# Main.net
KiCad netlist of a schematic drawn in Altium Designer
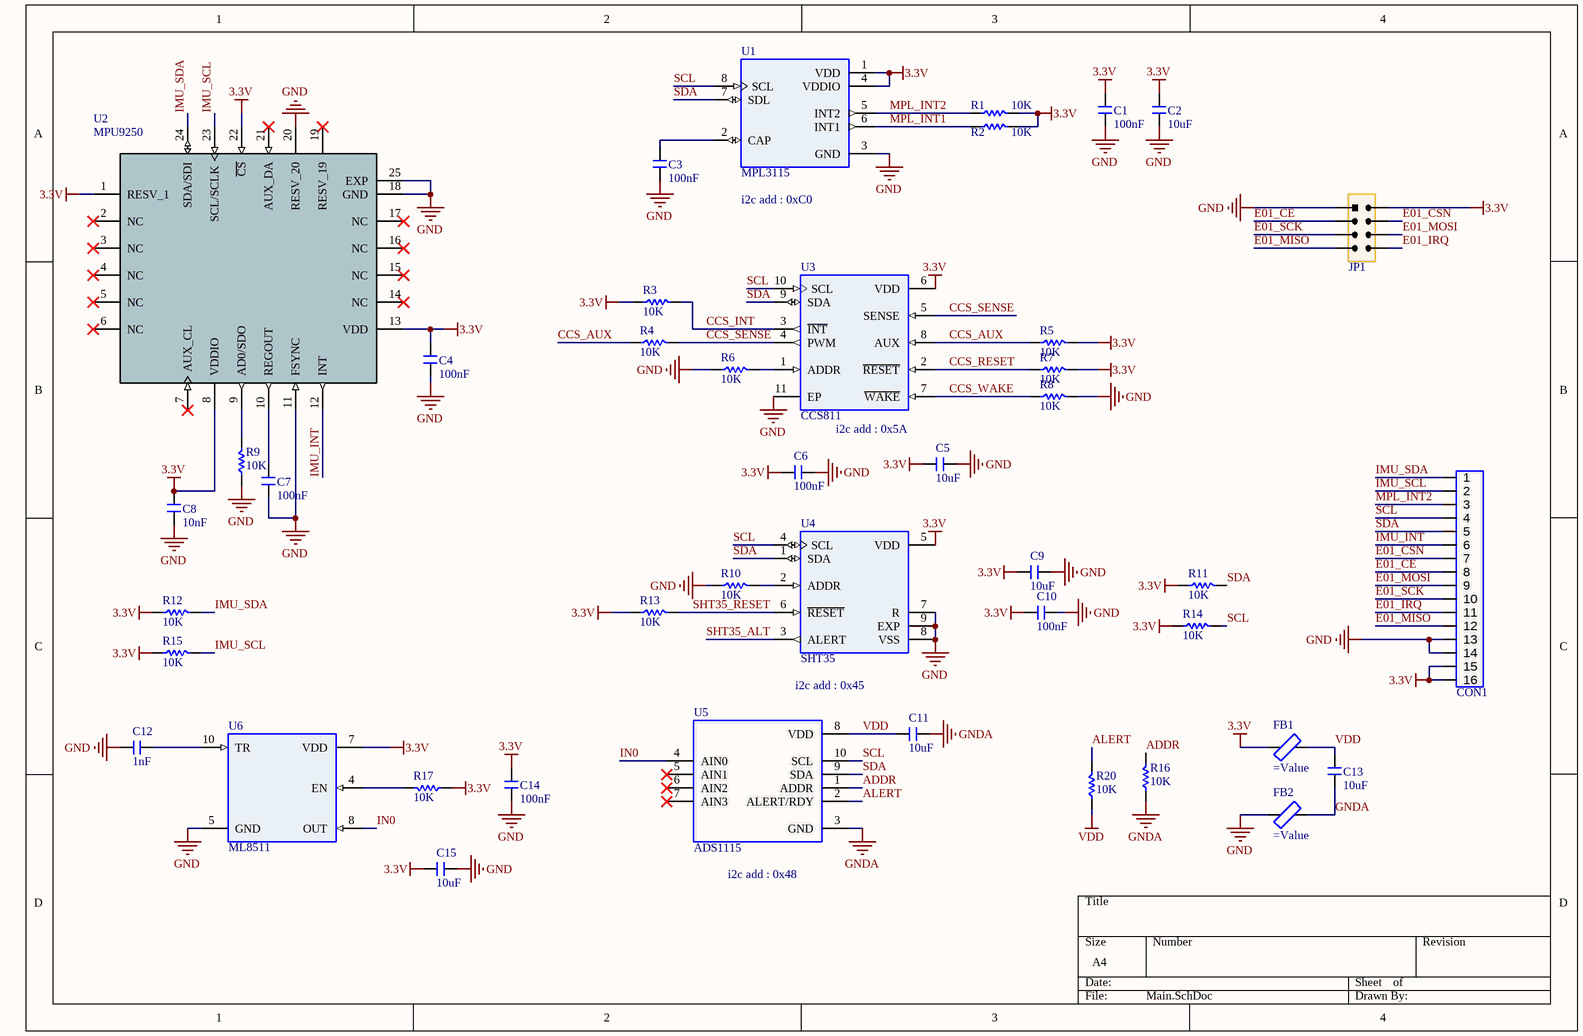
[diagram p0: Main.SchDoc]

(export (version "E")
  (design (tool "Eeschema 10.0.6"))
  (components
    (comp (ref "C1")
      (value "100nF")
      (footprint "C 0603")
      (description "Non-polar patch capacitor")
      (fields (field (name "版权归属") "源创客"))
      (libsource (lib "Passive (Resistor-Capacitor-Inductor-Veristor-Ferrite)") (part "C"))
    )
    (comp (ref "C2")
      (value "10uF")
      (footprint "C 0603")
      (description "Non-polar patch capacitor")
      (fields (field (name "版权归属") "源创客"))
      (libsource (lib "Passive (Resistor-Capacitor-Inductor-Veristor-Ferrite)") (part "C"))
    )
    (comp (ref "C3")
      (value "100nF")
      (footprint "C 0603")
      (description "Non-polar patch capacitor")
      (fields (field (name "版权归属") "源创客"))
      (libsource (lib "Passive (Resistor-Capacitor-Inductor-Veristor-Ferrite)") (part "C"))
    )
    (comp (ref "C4")
      (value "100nF")
      (footprint "C 0603")
      (description "Non-polar patch capacitor")
      (fields (field (name "版权归属") "源创客"))
      (libsource (lib "Passive (Resistor-Capacitor-Inductor-Veristor-Ferrite)") (part "C"))
    )
    (comp (ref "C5")
      (value "10uF")
      (footprint "C 0603")
      (description "Non-polar patch capacitor")
      (fields (field (name "版权归属") "源创客"))
      (libsource (lib "Passive (Resistor-Capacitor-Inductor-Veristor-Ferrite)") (part "C"))
    )
    (comp (ref "C6")
      (value "100nF")
      (footprint "C 0603")
      (description "Non-polar patch capacitor")
      (fields (field (name "版权归属") "源创客"))
      (libsource (lib "Passive (Resistor-Capacitor-Inductor-Veristor-Ferrite)") (part "C"))
    )
    (comp (ref "C7")
      (value "100nF")
      (footprint "C 0603")
      (description "Non-polar patch capacitor")
      (fields (field (name "版权归属") "源创客"))
      (libsource (lib "Passive (Resistor-Capacitor-Inductor-Veristor-Ferrite)") (part "C"))
    )
    (comp (ref "C8")
      (value "10nF")
      (footprint "C 0603")
      (description "Non-polar patch capacitor")
      (fields (field (name "版权归属") "源创客"))
      (libsource (lib "Passive (Resistor-Capacitor-Inductor-Veristor-Ferrite)") (part "C"))
    )
    (comp (ref "C9")
      (value "10uF")
      (footprint "C 0603")
      (description "Non-polar patch capacitor")
      (fields (field (name "版权归属") "源创客"))
      (libsource (lib "Passive (Resistor-Capacitor-Inductor-Veristor-Ferrite)") (part "C"))
    )
    (comp (ref "C10")
      (value "100nF")
      (footprint "C 0603")
      (description "Non-polar patch capacitor")
      (fields (field (name "版权归属") "源创客"))
      (libsource (lib "Passive (Resistor-Capacitor-Inductor-Veristor-Ferrite)") (part "C"))
    )
    (comp (ref "C11")
      (value "10uF")
      (footprint "C 0603")
      (description "Non-polar patch capacitor")
      (fields (field (name "版权归属") "源创客"))
      (libsource (lib "Passive (Resistor-Capacitor-Inductor-Veristor-Ferrite)") (part "C"))
    )
    (comp (ref "C12")
      (value "1nF")
      (footprint "C 0603")
      (description "Non-polar patch capacitor")
      (fields (field (name "版权归属") "源创客"))
      (libsource (lib "Passive (Resistor-Capacitor-Inductor-Veristor-Ferrite)") (part "C"))
    )
    (comp (ref "C13")
      (value "10uF")
      (footprint "C 0603")
      (description "Non-polar patch capacitor")
      (fields (field (name "版权归属") "源创客"))
      (libsource (lib "Passive (Resistor-Capacitor-Inductor-Veristor-Ferrite)") (part "C"))
    )
    (comp (ref "C14")
      (value "100nF")
      (footprint "C 0603")
      (description "Non-polar patch capacitor")
      (fields (field (name "版权归属") "源创客"))
      (libsource (lib "Passive (Resistor-Capacitor-Inductor-Veristor-Ferrite)") (part "C"))
    )
    (comp (ref "C15")
      (value "10uF")
      (footprint "C 0603")
      (description "Non-polar patch capacitor")
      (fields (field (name "版权归属") "源创客"))
      (libsource (lib "Passive (Resistor-Capacitor-Inductor-Veristor-Ferrite)") (part "C"))
    )
    (comp (ref "CON1")
      (value "FFC_0.5_16")
      (footprint "FFC_0.5_16")
      (description "FFC")
      (libsource (lib "FPC") (part "FFC_0.5_16"))
    )
    (comp (ref "FB1")
      (value "~")
      (footprint "F 0603")
      (description "Ferrite Bead")
      (fields (field (name "版权归属") "源创客"))
      (libsource (lib "Passive (Resistor-Capacitor-Inductor-Veristor-Ferrite)") (part "FB"))
    )
    (comp (ref "FB2")
      (value "~")
      (footprint "F 0603")
      (description "Ferrite Bead")
      (fields (field (name "版权归属") "源创客"))
      (libsource (lib "Passive (Resistor-Capacitor-Inductor-Veristor-Ferrite)") (part "FB"))
    )
    (comp (ref "JP1")
      (value "Header 4X2")
      (footprint "HDR-4X2")
      (description "4*2P Connector")
      (fields (field (name "版权归属") "源创客"))
      (libsource (lib "Connectors") (part "Header 4X2"))
    )
    (comp (ref "R1")
      (value "10K")
      (footprint "R 0603")
      (description "Chip resistor")
      (fields (field (name "版权归属") "源创客"))
      (libsource (lib "Passive (Resistor-Capacitor-Inductor-Veristor-Ferrite)") (part "R"))
    )
    (comp (ref "R2")
      (value "10K")
      (footprint "R 0603")
      (description "Chip resistor")
      (fields (field (name "版权归属") "源创客"))
      (libsource (lib "Passive (Resistor-Capacitor-Inductor-Veristor-Ferrite)") (part "R"))
    )
    (comp (ref "R3")
      (value "10K")
      (footprint "R 0603")
      (description "Chip resistor")
      (fields (field (name "版权归属") "源创客"))
      (libsource (lib "Passive (Resistor-Capacitor-Inductor-Veristor-Ferrite)") (part "R"))
    )
    (comp (ref "R4")
      (value "10K")
      (footprint "R 0603")
      (description "Chip resistor")
      (fields (field (name "版权归属") "源创客"))
      (libsource (lib "Passive (Resistor-Capacitor-Inductor-Veristor-Ferrite)") (part "R"))
    )
    (comp (ref "R5")
      (value "10K")
      (footprint "R 0603")
      (description "Chip resistor")
      (fields (field (name "版权归属") "源创客"))
      (libsource (lib "Passive (Resistor-Capacitor-Inductor-Veristor-Ferrite)") (part "R"))
    )
    (comp (ref "R6")
      (value "10K")
      (footprint "R 0603")
      (description "Chip resistor")
      (fields (field (name "版权归属") "源创客"))
      (libsource (lib "Passive (Resistor-Capacitor-Inductor-Veristor-Ferrite)") (part "R"))
    )
    (comp (ref "R7")
      (value "10K")
      (footprint "R 0603")
      (description "Chip resistor")
      (fields (field (name "版权归属") "源创客"))
      (libsource (lib "Passive (Resistor-Capacitor-Inductor-Veristor-Ferrite)") (part "R"))
    )
    (comp (ref "R8")
      (value "10K")
      (footprint "R 0603")
      (description "Chip resistor")
      (fields (field (name "版权归属") "源创客"))
      (libsource (lib "Passive (Resistor-Capacitor-Inductor-Veristor-Ferrite)") (part "R"))
    )
    (comp (ref "R9")
      (value "10K")
      (footprint "R 0603")
      (description "Chip resistor")
      (fields (field (name "版权归属") "源创客"))
      (libsource (lib "Passive (Resistor-Capacitor-Inductor-Veristor-Ferrite)") (part "R"))
    )
    (comp (ref "R10")
      (value "10K")
      (footprint "R 0603")
      (description "Chip resistor")
      (fields (field (name "版权归属") "源创客"))
      (libsource (lib "Passive (Resistor-Capacitor-Inductor-Veristor-Ferrite)") (part "R"))
    )
    (comp (ref "R11")
      (value "10K")
      (footprint "R 0603")
      (description "Chip resistor")
      (fields (field (name "版权归属") "源创客"))
      (libsource (lib "Passive (Resistor-Capacitor-Inductor-Veristor-Ferrite)") (part "R"))
    )
    (comp (ref "R12")
      (value "10K")
      (footprint "R 0603")
      (description "Chip resistor")
      (fields (field (name "版权归属") "源创客"))
      (libsource (lib "Passive (Resistor-Capacitor-Inductor-Veristor-Ferrite)") (part "R"))
    )
    (comp (ref "R13")
      (value "10K")
      (footprint "R 0603")
      (description "Chip resistor")
      (fields (field (name "版权归属") "源创客"))
      (libsource (lib "Passive (Resistor-Capacitor-Inductor-Veristor-Ferrite)") (part "R"))
    )
    (comp (ref "R14")
      (value "10K")
      (footprint "R 0603")
      (description "Chip resistor")
      (fields (field (name "版权归属") "源创客"))
      (libsource (lib "Passive (Resistor-Capacitor-Inductor-Veristor-Ferrite)") (part "R"))
    )
    (comp (ref "R15")
      (value "10K")
      (footprint "R 0603")
      (description "Chip resistor")
      (fields (field (name "版权归属") "源创客"))
      (libsource (lib "Passive (Resistor-Capacitor-Inductor-Veristor-Ferrite)") (part "R"))
    )
    (comp (ref "R16")
      (value "10K")
      (footprint "R 0603")
      (description "Chip resistor")
      (fields (field (name "版权归属") "源创客"))
      (libsource (lib "Passive (Resistor-Capacitor-Inductor-Veristor-Ferrite)") (part "R"))
    )
    (comp (ref "R17")
      (value "10K")
      (footprint "R 0603")
      (description "Chip resistor")
      (fields (field (name "版权归属") "源创客"))
      (libsource (lib "Passive (Resistor-Capacitor-Inductor-Veristor-Ferrite)") (part "R"))
    )
    (comp (ref "R20")
      (value "10K")
      (footprint "R 0603")
      (description "Chip resistor")
      (fields (field (name "版权归属") "源创客"))
      (libsource (lib "Passive (Resistor-Capacitor-Inductor-Veristor-Ferrite)") (part "R"))
    )
    (comp (ref "U1")
      (value "MPL3115")
      (footprint "MPL3115")
      (description "Pressure Sensor")
      (libsource (lib "Sensing Element") (part "MPL3115"))
    )
    (comp (ref "U2")
      (value "MPU9250")
      (footprint "QFN40-25N")
      (libsource (lib "Integrated Circuit") (part "MPU9250"))
    )
    (comp (ref "U3")
      (value "CCS811")
      (footprint "CCS811")
      (libsource (lib "Sensing Element") (part "CCS811"))
    )
    (comp (ref "U4") (value "SHT35") (footprint "SHT35") (libsource (lib "Sensing Element") (part "SHT35")))
    (comp (ref "U5")
      (value "ADS1115")
      (footprint "VSSOP10-N")
      (fields (field (name "版权归属") "源创客"))
      (libsource (lib "Integrated Circuit") (part "ADS1115"))
    )
    (comp (ref "U6")
      (value "ML8511")
      (footprint "ML8511")
      (description "UV Sensor")
      (libsource (lib "Sensing Element") (part "ML8511"))
    )
  )
  (nets
    (net (code "1") (name "/ADDR") (class "Default")
      (node (ref "R16") (pin "2") (pinfunction "2_2") (pintype "passive"))
      (node (ref "U5") (pin "1") (pinfunction "ADDR_1") (pintype "passive"))
    )
    (net (code "2") (name "/ALERT") (class "Default")
      (node (ref "R20") (pin "2") (pinfunction "2_2") (pintype "passive"))
      (node (ref "U5") (pin "2") (pinfunction "ALERT/RDY_2") (pintype "passive"))
    )
    (net (code "3") (name "/CCS_AUX") (class "Default")
      (node (ref "R4") (pin "1") (pinfunction "1_1") (pintype "passive"))
      (node (ref "R5") (pin "1") (pinfunction "1_1") (pintype "passive"))
      (node (ref "U3") (pin "8") (pinfunction "AUX_8") (pintype "input"))
    )
    (net (code "4") (name "/CCS_INT") (class "Default")
      (node (ref "R3") (pin "2") (pinfunction "2_2") (pintype "passive"))
      (node (ref "U3") (pin "3") (pinfunction "~{INT}_3") (pintype "output"))
    )
    (net (code "5") (name "/CCS_RESET") (class "Default")
      (node (ref "R7") (pin "1") (pinfunction "1_1") (pintype "passive"))
      (node (ref "U3") (pin "2") (pinfunction "~{RESET}_2") (pintype "input"))
    )
    (net (code "6") (name "/CCS_SENSE") (class "Default")
      (node (ref "R4") (pin "2") (pinfunction "2_2") (pintype "passive"))
      (node (ref "U3") (pin "4") (pinfunction "PWM_4") (pintype "output"))
      (node (ref "U3") (pin "5") (pinfunction "SENSE_5") (pintype "input"))
    )
    (net (code "7") (name "/CCS_WAKE") (class "Default")
      (node (ref "R8") (pin "1") (pinfunction "1_1") (pintype "passive"))
      (node (ref "U3") (pin "7") (pinfunction "~{WAKE}_7") (pintype "input"))
    )
    (net (code "8") (name "/E01_CE") (class "Default")
      (node (ref "CON1") (pin "8") (pinfunction "8_8") (pintype "passive"))
      (node (ref "JP1") (pin "3") (pintype "passive"))
    )
    (net (code "9") (name "/E01_CSN") (class "Default")
      (node (ref "CON1") (pin "7") (pinfunction "7_7") (pintype "passive"))
      (node (ref "JP1") (pin "4") (pintype "passive"))
    )
    (net (code "10") (name "/E01_IRQ") (class "Default")
      (node (ref "CON1") (pin "11") (pinfunction "11_11") (pintype "passive"))
      (node (ref "JP1") (pin "8") (pintype "passive"))
    )
    (net (code "11") (name "/E01_MISO") (class "Default")
      (node (ref "CON1") (pin "12") (pinfunction "12_12") (pintype "passive"))
      (node (ref "JP1") (pin "7") (pintype "passive"))
    )
    (net (code "12") (name "/E01_MOSI") (class "Default")
      (node (ref "CON1") (pin "9") (pinfunction "9_9") (pintype "passive"))
      (node (ref "JP1") (pin "6") (pintype "passive"))
    )
    (net (code "13") (name "/E01_SCK") (class "Default")
      (node (ref "CON1") (pin "10") (pinfunction "10_10") (pintype "passive"))
      (node (ref "JP1") (pin "5") (pintype "passive"))
    )
    (net (code "14") (name "/IMU_INT") (class "Default")
      (node (ref "CON1") (pin "6") (pinfunction "6_6") (pintype "passive"))
      (node (ref "U2") (pin "12") (pinfunction "INT_12") (pintype "output"))
    )
    (net (code "15") (name "/IMU_SCL") (class "Default")
      (node (ref "CON1") (pin "2") (pinfunction "2_2") (pintype "passive"))
      (node (ref "R15") (pin "2") (pinfunction "2_2") (pintype "passive"))
      (node (ref "U2") (pin "23") (pinfunction "SCL/SCLK_23") (pintype "input"))
    )
    (net (code "16") (name "/IMU_SDA") (class "Default")
      (node (ref "CON1") (pin "1") (pinfunction "1_1") (pintype "passive"))
      (node (ref "R12") (pin "2") (pinfunction "2_2") (pintype "passive"))
      (node (ref "U2") (pin "24") (pinfunction "SDA/SDI_24") (pintype "bidirectional"))
    )
    (net (code "17") (name "/IN0") (class "Default")
      (node (ref "U5") (pin "4") (pinfunction "AIN0_4") (pintype "passive"))
      (node (ref "U6") (pin "8") (pinfunction "OUT_8") (pintype "input"))
    )
    (net (code "18") (name "/MPL_INT1") (class "Default")
      (node (ref "R2") (pin "1") (pinfunction "1_1") (pintype "passive"))
      (node (ref "U1") (pin "6") (pinfunction "INT1_6") (pintype "output"))
    )
    (net (code "19") (name "/MPL_INT2") (class "Default")
      (node (ref "CON1") (pin "3") (pinfunction "3_3") (pintype "passive"))
      (node (ref "R1") (pin "1") (pinfunction "1_1") (pintype "passive"))
      (node (ref "U1") (pin "5") (pinfunction "INT2_5") (pintype "output"))
    )
    (net (code "20") (name "/SCL") (class "Default")
      (node (ref "CON1") (pin "4") (pinfunction "4_4") (pintype "passive"))
      (node (ref "R14") (pin "2") (pinfunction "2_2") (pintype "passive"))
      (node (ref "U1") (pin "8") (pinfunction "SCL_8") (pintype "input"))
      (node (ref "U3") (pin "10") (pinfunction "SCL_10") (pintype "input"))
      (node (ref "U4") (pin "4") (pinfunction "SCL_4") (pintype "bidirectional"))
      (node (ref "U5") (pin "10") (pinfunction "SCL_10") (pintype "passive"))
    )
    (net (code "21") (name "/SDA") (class "Default")
      (node (ref "CON1") (pin "5") (pinfunction "5_5") (pintype "passive"))
      (node (ref "R11") (pin "2") (pinfunction "2_2") (pintype "passive"))
      (node (ref "U1") (pin "7") (pinfunction "SDL_7") (pintype "bidirectional"))
      (node (ref "U3") (pin "9") (pinfunction "SDA_9") (pintype "bidirectional"))
      (node (ref "U4") (pin "1") (pinfunction "SDA_1") (pintype "bidirectional"))
      (node (ref "U5") (pin "9") (pinfunction "SDA_9") (pintype "passive"))
    )
    (net (code "22") (name "/SHT35_ALT") (class "Default")
      (node (ref "U4") (pin "3") (pinfunction "ALERT_3") (pintype "output"))
    )
    (net (code "23") (name "/SHT35_RESET") (class "Default")
      (node (ref "R13") (pin "2") (pinfunction "2_2") (pintype "passive"))
      (node (ref "U4") (pin "6") (pinfunction "~{RESET}_6") (pintype "input"))
    )
    (net (code "24") (name "3.3V") (class "Default")
      (node (ref "C1") (pin "2") (pinfunction "2_2") (pintype "passive"))
      (node (ref "C10") (pin "1") (pinfunction "1_1") (pintype "passive"))
      (node (ref "C14") (pin "2") (pinfunction "2_2") (pintype "passive"))
      (node (ref "C15") (pin "2") (pinfunction "2_2") (pintype "passive"))
      (node (ref "C2") (pin "2") (pinfunction "2_2") (pintype "passive"))
      (node (ref "C4") (pin "1") (pinfunction "1_1") (pintype "passive"))
      (node (ref "C5") (pin "2") (pinfunction "2_2") (pintype "passive"))
      (node (ref "C6") (pin "1") (pinfunction "1_1") (pintype "passive"))
      (node (ref "C8") (pin "1") (pinfunction "1_1") (pintype "passive"))
      (node (ref "C9") (pin "2") (pinfunction "2_2") (pintype "passive"))
      (node (ref "CON1") (pin "15") (pinfunction "15_15") (pintype "passive"))
      (node (ref "CON1") (pin "16") (pinfunction "16_16") (pintype "passive"))
      (node (ref "FB1") (pin "1") (pinfunction "1_1") (pintype "passive"))
      (node (ref "JP1") (pin "2") (pintype "passive"))
      (node (ref "R1") (pin "2") (pinfunction "2_2") (pintype "passive"))
      (node (ref "R11") (pin "1") (pinfunction "1_1") (pintype "passive"))
      (node (ref "R12") (pin "1") (pinfunction "1_1") (pintype "passive"))
      (node (ref "R13") (pin "1") (pinfunction "1_1") (pintype "passive"))
      (node (ref "R14") (pin "1") (pinfunction "1_1") (pintype "passive"))
      (node (ref "R15") (pin "1") (pinfunction "1_1") (pintype "passive"))
      (node (ref "R17") (pin "1") (pinfunction "1_1") (pintype "passive"))
      (node (ref "R2") (pin "2") (pinfunction "2_2") (pintype "passive"))
      (node (ref "R3") (pin "1") (pinfunction "1_1") (pintype "passive"))
      (node (ref "R5") (pin "2") (pinfunction "2_2") (pintype "passive"))
      (node (ref "R7") (pin "2") (pinfunction "2_2") (pintype "passive"))
      (node (ref "U1") (pin "1") (pinfunction "VDD_1") (pintype "power_in"))
      (node (ref "U1") (pin "4") (pinfunction "VDDIO_4") (pintype "power_in"))
      (node (ref "U2") (pin "1") (pinfunction "RESV_1_1") (pintype "power_in"))
      (node (ref "U2") (pin "13") (pinfunction "VDD_13") (pintype "power_in"))
      (node (ref "U2") (pin "22") (pinfunction "~{CS}_22") (pintype "input"))
      (node (ref "U2") (pin "8") (pinfunction "VDDIO_8") (pintype "power_in"))
      (node (ref "U3") (pin "6") (pinfunction "VDD_6") (pintype "power_in"))
      (node (ref "U4") (pin "5") (pinfunction "VDD_5") (pintype "power_in"))
      (node (ref "U6") (pin "7") (pinfunction "VDD_7") (pintype "power_in"))
    )
    (net (code "25") (name "GND") (class "Default")
      (node (ref "C1") (pin "1") (pinfunction "1_1") (pintype "passive"))
      (node (ref "C10") (pin "2") (pinfunction "2_2") (pintype "passive"))
      (node (ref "C12") (pin "1") (pinfunction "1_1") (pintype "passive"))
      (node (ref "C14") (pin "1") (pinfunction "1_1") (pintype "passive"))
      (node (ref "C15") (pin "1") (pinfunction "1_1") (pintype "passive"))
      (node (ref "C2") (pin "1") (pinfunction "1_1") (pintype "passive"))
      (node (ref "C3") (pin "1") (pinfunction "1_1") (pintype "passive"))
      (node (ref "C4") (pin "2") (pinfunction "2_2") (pintype "passive"))
      (node (ref "C5") (pin "1") (pinfunction "1_1") (pintype "passive"))
      (node (ref "C6") (pin "2") (pinfunction "2_2") (pintype "passive"))
      (node (ref "C7") (pin "2") (pinfunction "2_2") (pintype "passive"))
      (node (ref "C8") (pin "2") (pinfunction "2_2") (pintype "passive"))
      (node (ref "C9") (pin "1") (pinfunction "1_1") (pintype "passive"))
      (node (ref "CON1") (pin "13") (pinfunction "13_13") (pintype "passive"))
      (node (ref "CON1") (pin "14") (pinfunction "14_14") (pintype "passive"))
      (node (ref "FB2") (pin "1") (pinfunction "1_1") (pintype "passive"))
      (node (ref "JP1") (pin "1") (pintype "passive"))
      (node (ref "R10") (pin "1") (pinfunction "1_1") (pintype "passive"))
      (node (ref "R6") (pin "1") (pinfunction "1_1") (pintype "passive"))
      (node (ref "R8") (pin "2") (pinfunction "2_2") (pintype "passive"))
      (node (ref "R9") (pin "1") (pinfunction "1_1") (pintype "passive"))
      (node (ref "U1") (pin "3") (pinfunction "GND_3") (pintype "power_in"))
      (node (ref "U2") (pin "11") (pinfunction "FSYNC_11") (pintype "input"))
      (node (ref "U2") (pin "18") (pinfunction "GND_18") (pintype "power_in"))
      (node (ref "U2") (pin "20") (pinfunction "RESV_20_20") (pintype "power_in"))
      (node (ref "U2") (pin "25") (pinfunction "EXP_25") (pintype "passive"))
      (node (ref "U3") (pin "11") (pinfunction "EP_11") (pintype "power_in"))
      (node (ref "U4") (pin "7") (pinfunction "R_7") (pintype "passive"))
      (node (ref "U4") (pin "8") (pinfunction "VSS_8") (pintype "power_in"))
      (node (ref "U4") (pin "9") (pinfunction "EXP_9") (pintype "passive"))
      (node (ref "U6") (pin "5") (pinfunction "GND_5") (pintype "power_in"))
    )
    (net (code "26") (name "GNDA") (class "Default")
      (node (ref "C11") (pin "1") (pinfunction "1_1") (pintype "passive"))
      (node (ref "C13") (pin "2") (pinfunction "2_2") (pintype "passive"))
      (node (ref "FB2") (pin "2") (pinfunction "2_2") (pintype "passive"))
      (node (ref "R16") (pin "1") (pinfunction "1_1") (pintype "passive"))
      (node (ref "U5") (pin "3") (pinfunction "GND_3") (pintype "passive"))
    )
    (net (code "27") (name "Net-(U1-CAP)") (class "Default")
      (node (ref "C3") (pin "2") (pinfunction "2_2") (pintype "passive"))
      (node (ref "U1") (pin "2") (pinfunction "CAP_2") (pintype "bidirectional"))
    )
    (net (code "28") (name "Net-(U2-AD0{slash}SDO)") (class "Default")
      (node (ref "R9") (pin "2") (pinfunction "2_2") (pintype "passive"))
      (node (ref "U2") (pin "9") (pinfunction "AD0/SDO_9") (pintype "output"))
    )
    (net (code "29") (name "Net-(U2-REGOUT)") (class "Default")
      (node (ref "C7") (pin "1") (pinfunction "1_1") (pintype "passive"))
      (node (ref "U2") (pin "10") (pinfunction "REGOUT_10") (pintype "output"))
    )
    (net (code "30") (name "Net-(U3-ADDR)") (class "Default")
      (node (ref "R6") (pin "2") (pinfunction "2_2") (pintype "passive"))
      (node (ref "U3") (pin "1") (pinfunction "ADDR_1") (pintype "input"))
    )
    (net (code "31") (name "Net-(U4-ADDR)") (class "Default")
      (node (ref "R10") (pin "2") (pinfunction "2_2") (pintype "passive"))
      (node (ref "U4") (pin "2") (pinfunction "ADDR_2") (pintype "input"))
    )
    (net (code "32") (name "Net-(U6-EN)") (class "Default")
      (node (ref "R17") (pin "2") (pinfunction "2_2") (pintype "passive"))
      (node (ref "U6") (pin "4") (pinfunction "EN_4") (pintype "input"))
    )
    (net (code "33") (name "Net-(U6-TR)") (class "Default")
      (node (ref "C12") (pin "2") (pinfunction "2_2") (pintype "passive"))
      (node (ref "U6") (pin "10") (pinfunction "TR_10") (pintype "input"))
    )
    (net (code "34") (name "VDD") (class "Default")
      (node (ref "C11") (pin "2") (pinfunction "2_2") (pintype "passive"))
      (node (ref "C13") (pin "1") (pinfunction "1_1") (pintype "passive"))
      (node (ref "FB1") (pin "2") (pinfunction "2_2") (pintype "passive"))
      (node (ref "R20") (pin "1") (pinfunction "1_1") (pintype "passive"))
      (node (ref "U5") (pin "8") (pinfunction "VDD_8") (pintype "passive"))
    )
    (net (code "35") (name "unconnected-(U2-AUX_CL-Pad7)") (class "Default")
      (node (ref "U2") (pin "7") (pinfunction "AUX_CL_7") (pintype "input+no_connect"))
    )
    (net (code "36") (name "unconnected-(U2-AUX_DA-Pad21)") (class "Default")
      (node (ref "U2") (pin "21") (pinfunction "AUX_DA_21") (pintype "input+no_connect"))
    )
    (net (code "37") (name "unconnected-(U2-NC-Pad2)") (class "Default")
      (node (ref "U2") (pin "2") (pinfunction "NC_2") (pintype "passive+no_connect"))
    )
    (net (code "38") (name "unconnected-(U2-NC-Pad3)") (class "Default")
      (node (ref "U2") (pin "3") (pinfunction "NC_3") (pintype "passive+no_connect"))
    )
    (net (code "39") (name "unconnected-(U2-NC-Pad4)") (class "Default")
      (node (ref "U2") (pin "4") (pinfunction "NC_4") (pintype "passive+no_connect"))
    )
    (net (code "40") (name "unconnected-(U2-NC-Pad5)") (class "Default")
      (node (ref "U2") (pin "5") (pinfunction "NC_5") (pintype "passive+no_connect"))
    )
    (net (code "41") (name "unconnected-(U2-NC-Pad6)") (class "Default")
      (node (ref "U2") (pin "6") (pinfunction "NC_6") (pintype "passive+no_connect"))
    )
    (net (code "42") (name "unconnected-(U2-NC-Pad14)") (class "Default")
      (node (ref "U2") (pin "14") (pinfunction "NC_14") (pintype "passive+no_connect"))
    )
    (net (code "43") (name "unconnected-(U2-NC-Pad15)") (class "Default")
      (node (ref "U2") (pin "15") (pinfunction "NC_15") (pintype "passive+no_connect"))
    )
    (net (code "44") (name "unconnected-(U2-NC-Pad16)") (class "Default")
      (node (ref "U2") (pin "16") (pinfunction "NC_16") (pintype "passive+no_connect"))
    )
    (net (code "45") (name "unconnected-(U2-NC-Pad17)") (class "Default")
      (node (ref "U2") (pin "17") (pinfunction "NC_17") (pintype "passive+no_connect"))
    )
    (net (code "46") (name "unconnected-(U2-RESV_19-Pad19)") (class "Default")
      (node (ref "U2") (pin "19") (pinfunction "RESV_19_19") (pintype "passive+no_connect"))
    )
    (net (code "47") (name "unconnected-(U5-AIN1-Pad5)") (class "Default")
      (node (ref "U5") (pin "5") (pinfunction "AIN1_5") (pintype "passive+no_connect"))
    )
    (net (code "48") (name "unconnected-(U5-AIN2-Pad6)") (class "Default")
      (node (ref "U5") (pin "6") (pinfunction "AIN2_6") (pintype "passive+no_connect"))
    )
    (net (code "49") (name "unconnected-(U5-AIN3-Pad7)") (class "Default")
      (node (ref "U5") (pin "7") (pinfunction "AIN3_7") (pintype "passive+no_connect"))
    )
  )
)
